# CH32X035G8U-R0.net
KiCad netlist of a schematic drawn in Altium Designer
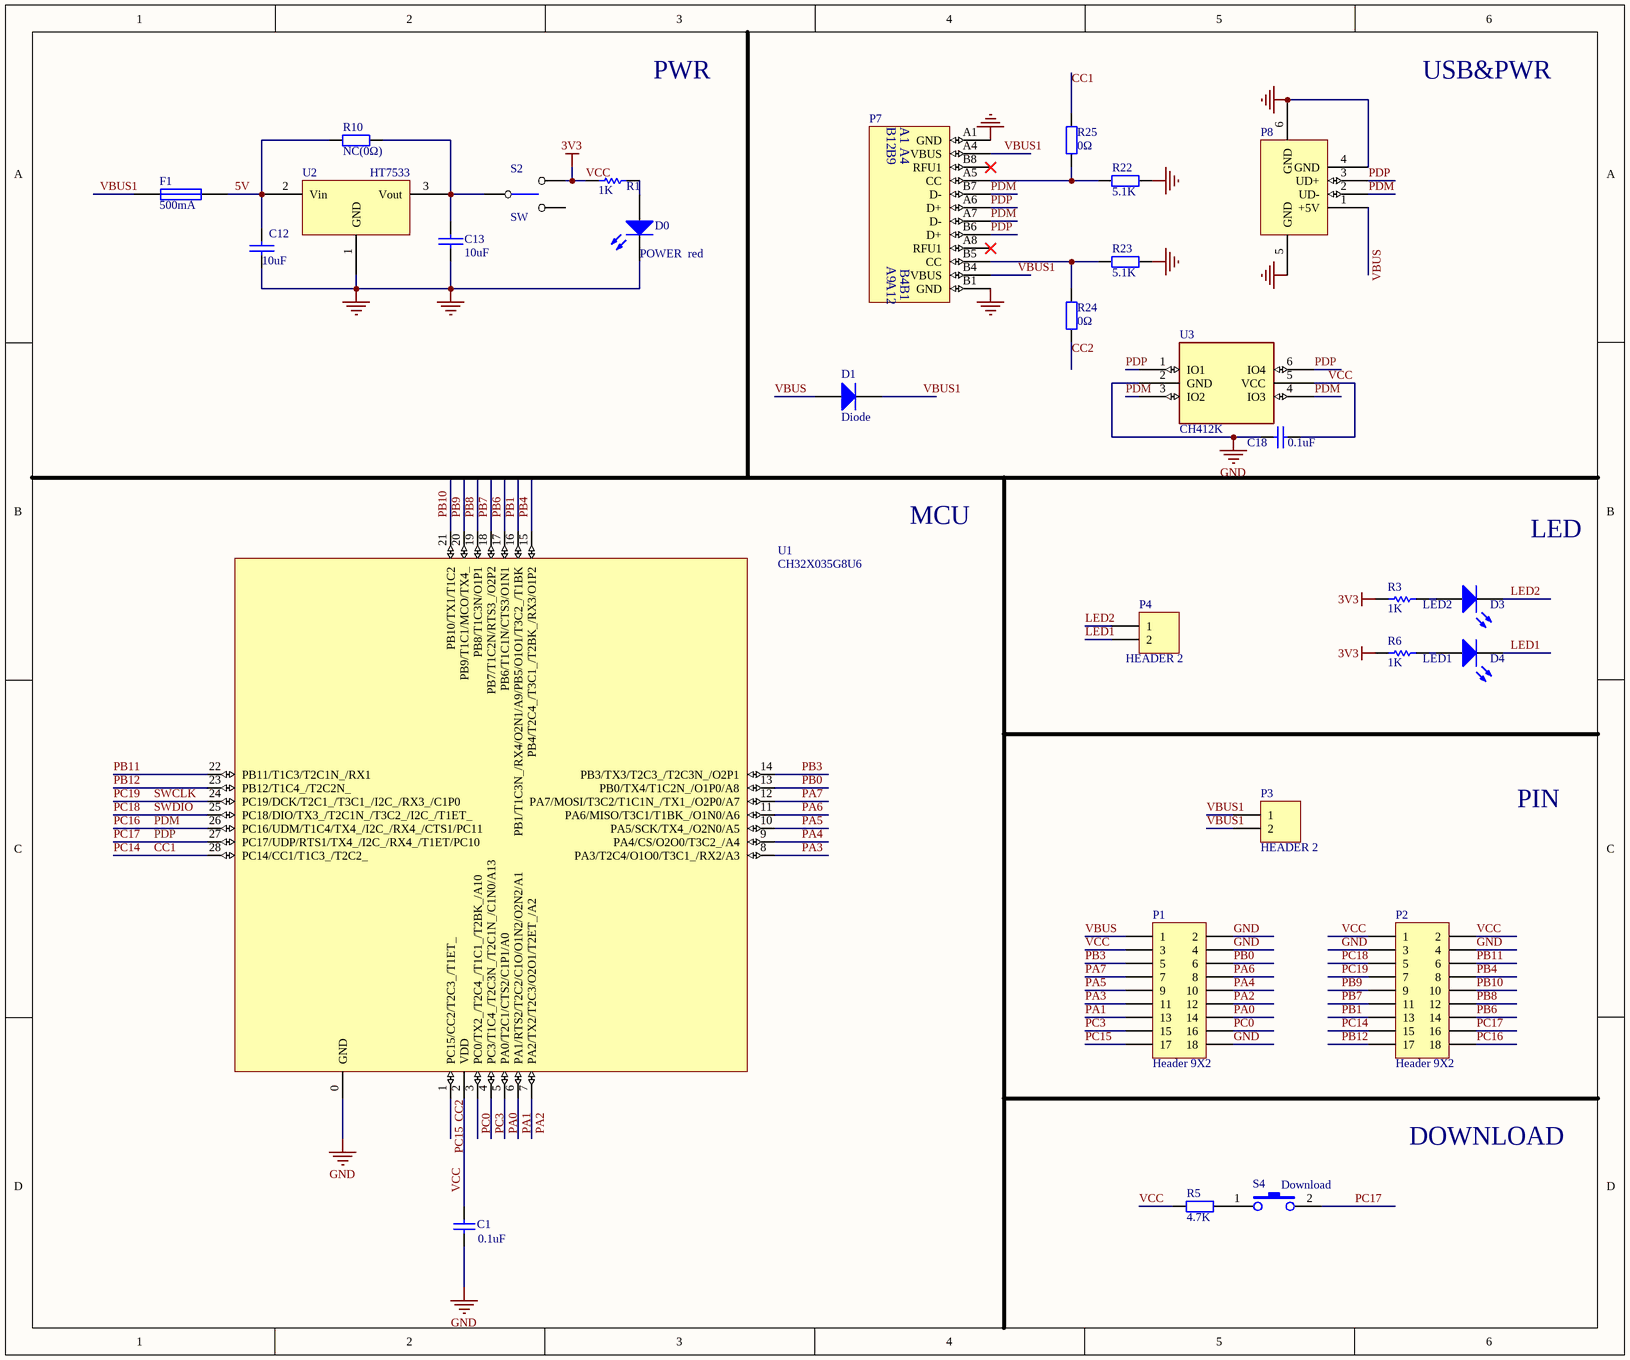
[diagram p0: CH32X035G8U-R0.SchDoc]

(export (version "E")
  (design (tool "Eeschema 10.0.6"))
  (components
    (comp (ref "C1")
      (value "0.1uF")
      (footprint "0603_C")
      (description "Capacitor")
      (libsource (lib "Miscellaneous Devices") (part "Cap"))
    )
    (comp (ref "C12")
      (value "10uF")
      (footprint "0603_C")
      (description "Capacitor")
      (libsource (lib "*") (part "CAP"))
    )
    (comp (ref "C13")
      (value "10uF")
      (footprint "0603_C")
      (description "Capacitor")
      (libsource (lib "*") (part "CAP"))
    )
    (comp (ref "C18")
      (value "0.1uF")
      (footprint "0603_C")
      (description "Capacitor")
      (libsource (lib "Miscellaneous Devices") (part "Cap"))
    )
    (comp (ref "D0")
      (value "POWER  red")
      (footprint "0603+")
      (description "Typical INFRARED GaAs LED")
      (fields (field (name "PUBLISHER") "Altium Limited"))
      (libsource (lib "*") (part "LED0"))
    )
    (comp (ref "D1")
      (value "Diode")
      (footprint "SOD-123")
      (description "Default Diode")
      (fields (field (name "PUBLISHER") "Altium Limited"))
      (libsource (lib "Miscellaneous Devices") (part "Diode"))
    )
    (comp (ref "D3")
      (value "LED2")
      (footprint "0603+")
      (description "Typical INFRARED GaAs LED")
      (fields (field (name "PUBLISHER") "Altium Limited"))
      (libsource (lib "*") (part "LED0"))
    )
    (comp (ref "D4")
      (value "LED1")
      (footprint "0603+")
      (description "Typical INFRARED GaAs LED")
      (fields (field (name "PUBLISHER") "Altium Limited"))
      (libsource (lib "*") (part "LED0"))
    )
    (comp (ref "F1")
      (value "500mA")
      (footprint "0603")
      (description "Fuse")
      (libsource (lib "*") (part "FUSE1"))
    )
    (comp (ref "P1")
      (value "Header 9X2")
      (footprint "IDC18-2.54mm")
      (description "Header, 9-Pin, Dual row")
      (fields (field (name "PUBLISHER") "Altium Limited"))
      (libsource (lib "Miscellaneous Connectors") (part "Header 9X2"))
    )
    (comp (ref "P2")
      (value "Header 9X2")
      (footprint "IDC18-2.54mm")
      (description "Header, 9-Pin, Dual row")
      (fields (field (name "PUBLISHER") "Altium Limited"))
      (libsource (lib "Miscellaneous Connectors") (part "Header 9X2"))
    )
    (comp (ref "P3")
      (value "HEADER 2")
      (footprint "MYPCB:SIP2-2.54mm")
      (description "Header, 2-Pin")
      (libsource (lib "wch_sch_others") (part "HEADER 2"))
    )
    (comp (ref "P4")
      (value "HEADER 2")
      (footprint "MYPCB:SIP2-2.54mm")
      (description "Header, 2-Pin")
      (libsource (lib "wch_sch_others") (part "HEADER 2"))
    )
    (comp (ref "P7")
      (value "TYPE-C")
      (footprint "TYPE-C-Receptacle-2.0")
      (libsource (lib "*") (part "TYPE-C1"))
    )
    (comp (ref "P8")
      (value "USB_A")
      (footprint "USBAF")
      (description "USB Port")
      (libsource (lib "*") (part "USB"))
    )
    (comp (ref "R1")
      (value "1K")
      (footprint "0603")
      (description "Semiconductor Resistor")
      (fields (field (name "PUBLISHER") "Altium Limited"))
      (libsource (lib "*") (part "Res Semi"))
    )
    (comp (ref "R3")
      (value "1K")
      (footprint "0603")
      (description "Semiconductor Resistor")
      (fields (field (name "PUBLISHER") "Altium Limited"))
      (libsource (lib "*") (part "Res Semi"))
    )
    (comp (ref "R5")
      (value "4.7K")
      (footprint "0603")
      (description "Resistor")
      (libsource (lib "Miscellaneous Devices") (part "Res2"))
    )
    (comp (ref "R6")
      (value "1K")
      (footprint "0603")
      (description "Semiconductor Resistor")
      (fields (field (name "PUBLISHER") "Altium Limited"))
      (libsource (lib "*") (part "Res Semi"))
    )
    (comp (ref "R10")
      (value "NC(0Ω)")
      (footprint "0603")
      (description "Resistor")
      (fields (field (name "PUBLISHER") "Altium Limited"))
      (libsource (lib "*") (part "Res2"))
    )
    (comp (ref "R22")
      (value "5.1K")
      (footprint "0603")
      (description "Resistor")
      (libsource (lib "Miscellaneous Devices") (part "Res2"))
    )
    (comp (ref "R23")
      (value "5.1K")
      (footprint "0603")
      (description "Resistor")
      (libsource (lib "Miscellaneous Devices") (part "Res2"))
    )
    (comp (ref "R24")
      (value "0Ω")
      (footprint "0603")
      (description "Resistor")
      (libsource (lib "") (part "Res2_1"))
    )
    (comp (ref "R25")
      (value "0Ω")
      (footprint "0603")
      (description "Resistor")
      (libsource (lib "") (part "Res2_1"))
    )
    (comp (ref "S2") (value "SW") (footprint "SW1") (libsource (lib "*") (part "SW")))
    (comp (ref "S4")
      (value "Download")
      (footprint "SMD_6.1x3.65x2.5mm-KEY")
      (libsource (lib "wch_sch_others") (part "KEY1"))
    )
    (comp (ref "U1")
      (value "CH32X035G8U6")
      (footprint "QFN28_4X4")
      (description "RISC-V MCU with USB/PD/ADC/SPI/I2C/UART/OA/CMP")
      (libsource (lib "CHXXX") (part "CH32X035G8U6"))
    )
    (comp (ref "U2")
      (value "HT7533")
      (footprint "SOT-89")
      (libsource (lib "wch_sch_others") (part "1117-3.3V"))
    )
    (comp (ref "U3")
      (value "CH412K")
      (footprint "SOT-363")
      (description "Qaud ESD protect, high speed")
      (libsource (lib "CHXXX") (part "CH412K"))
    )
  )
  (nets
    (net (code "1") (name "/5V") (class "Default")
      (node (ref "C12") (pin "1") (pinfunction "1_1") (pintype "passive"))
      (node (ref "F1") (pin "2") (pinfunction "2_2") (pintype "passive"))
      (node (ref "R10") (pin "2") (pinfunction "2_2") (pintype "passive"))
      (node (ref "U2") (pin "2") (pinfunction "Vin_2") (pintype "passive"))
    )
    (net (code "3") (name "/CC1") (class "Default")
      (node (ref "P2") (pin "15") (pinfunction "15_15") (pintype "passive"))
      (node (ref "R25") (pin "2") (pinfunction "2_2") (pintype "passive"))
      (node (ref "U1") (pin "28") (pinfunction "PC14/CC1/T1C3_/T2C2__28") (pintype "bidirectional"))
    )
    (net (code "4") (name "/CC2") (class "Default")
      (node (ref "P1") (pin "17") (pinfunction "17_17") (pintype "passive"))
      (node (ref "R24") (pin "1") (pinfunction "1_1") (pintype "passive"))
      (node (ref "U1") (pin "1") (pinfunction "PC15/CC2/T2C3_/T1ET__1") (pintype "bidirectional"))
    )
    (net (code "5") (name "/LED1") (class "Default")
      (node (ref "D4") (pin "2") (pinfunction "K_2") (pintype "passive"))
      (node (ref "P4") (pin "2") (pinfunction "2_2") (pintype "passive"))
    )
    (net (code "6") (name "/LED2") (class "Default")
      (node (ref "D3") (pin "2") (pinfunction "K_2") (pintype "passive"))
      (node (ref "P4") (pin "1") (pinfunction "1_1") (pintype "passive"))
    )
    (net (code "7") (name "/PA0") (class "Default")
      (node (ref "P1") (pin "14") (pinfunction "14_14") (pintype "passive"))
      (node (ref "U1") (pin "5") (pinfunction "PA0/T2C1/CTS2/C1P1/A0_5") (pintype "bidirectional"))
    )
    (net (code "8") (name "/PA1") (class "Default")
      (node (ref "P1") (pin "13") (pinfunction "13_13") (pintype "passive"))
      (node (ref "U1") (pin "6") (pinfunction "PA1/RTS2/T2C2/C1O/O1N2/O2N2/A1_6") (pintype "bidirectional"))
    )
    (net (code "9") (name "/PA2") (class "Default")
      (node (ref "P1") (pin "12") (pinfunction "12_12") (pintype "passive"))
      (node (ref "U1") (pin "7") (pinfunction "PA2/TX2/T2C3/O2O1/T2ET_/A2_7") (pintype "bidirectional"))
    )
    (net (code "10") (name "/PA3") (class "Default")
      (node (ref "P1") (pin "11") (pinfunction "11_11") (pintype "passive"))
      (node (ref "U1") (pin "8") (pinfunction "PA3/T2C4/O1O0/T3C1_/RX2/A3_8") (pintype "bidirectional"))
    )
    (net (code "11") (name "/PA4") (class "Default")
      (node (ref "P1") (pin "10") (pinfunction "10_10") (pintype "passive"))
      (node (ref "U1") (pin "9") (pinfunction "PA4/CS/O2O0/T3C2_/A4_9") (pintype "bidirectional"))
    )
    (net (code "12") (name "/PA5") (class "Default")
      (node (ref "P1") (pin "9") (pinfunction "9_9") (pintype "passive"))
      (node (ref "U1") (pin "10") (pinfunction "PA5/SCK/TX4_/O2N0/A5_10") (pintype "bidirectional"))
    )
    (net (code "13") (name "/PA6") (class "Default")
      (node (ref "P1") (pin "8") (pinfunction "8_8") (pintype "passive"))
      (node (ref "U1") (pin "11") (pinfunction "PA6/MISO/T3C1/T1BK_/O1N0/A6_11") (pintype "bidirectional"))
    )
    (net (code "14") (name "/PA7") (class "Default")
      (node (ref "P1") (pin "7") (pinfunction "7_7") (pintype "passive"))
      (node (ref "U1") (pin "12") (pinfunction "PA7/MOSI/T3C2/T1C1N_/TX1_/O2P0/A7_12") (pintype "bidirectional"))
    )
    (net (code "15") (name "/PB0") (class "Default")
      (node (ref "P1") (pin "6") (pinfunction "6_6") (pintype "passive"))
      (node (ref "U1") (pin "13") (pinfunction "PB0/TX4/T1C2N_/O1P0/A8_13") (pintype "bidirectional"))
    )
    (net (code "16") (name "/PB1") (class "Default")
      (node (ref "P2") (pin "13") (pinfunction "13_13") (pintype "passive"))
      (node (ref "U1") (pin "16") (pinfunction "PB1/T1C3N_/RX4/O2N1/A9/PB5/O1O1/T3C2_/T1BK_16") (pintype "bidirectional"))
    )
    (net (code "17") (name "/PB3") (class "Default")
      (node (ref "P1") (pin "5") (pinfunction "5_5") (pintype "passive"))
      (node (ref "U1") (pin "14") (pinfunction "PB3/TX3/T2C3_/T2C3N_/O2P1_14") (pintype "bidirectional"))
    )
    (net (code "18") (name "/PB4") (class "Default")
      (node (ref "P2") (pin "8") (pinfunction "8_8") (pintype "passive"))
      (node (ref "U1") (pin "15") (pinfunction "PB4/T2C4_/T3C1_/T2BK_/RX3/O1P2_15") (pintype "bidirectional"))
    )
    (net (code "19") (name "/PB6") (class "Default")
      (node (ref "P2") (pin "14") (pinfunction "14_14") (pintype "passive"))
      (node (ref "U1") (pin "17") (pinfunction "PB6/T1C1N/CTS3/O1N1_17") (pintype "bidirectional"))
    )
    (net (code "20") (name "/PB7") (class "Default")
      (node (ref "P2") (pin "11") (pinfunction "11_11") (pintype "passive"))
      (node (ref "U1") (pin "18") (pinfunction "PB7/T1C2N/RTS3_/O2P2_18") (pintype "bidirectional"))
    )
    (net (code "21") (name "/PB8") (class "Default")
      (node (ref "P2") (pin "12") (pinfunction "12_12") (pintype "passive"))
      (node (ref "U1") (pin "19") (pinfunction "PB8/T1C3N/O1P1_19") (pintype "bidirectional"))
    )
    (net (code "22") (name "/PB9") (class "Default")
      (node (ref "P2") (pin "9") (pinfunction "9_9") (pintype "passive"))
      (node (ref "U1") (pin "20") (pinfunction "PB9/T1C1/MCO/TX4__20") (pintype "bidirectional"))
    )
    (net (code "23") (name "/PB10") (class "Default")
      (node (ref "P2") (pin "10") (pinfunction "10_10") (pintype "passive"))
      (node (ref "U1") (pin "21") (pinfunction "PB10/TX1/T1C2_21") (pintype "bidirectional"))
    )
    (net (code "24") (name "/PB11") (class "Default")
      (node (ref "P2") (pin "6") (pinfunction "6_6") (pintype "passive"))
      (node (ref "U1") (pin "22") (pinfunction "PB11/T1C3/T2C1N_/RX1_22") (pintype "bidirectional"))
    )
    (net (code "25") (name "/PB12") (class "Default")
      (node (ref "P2") (pin "17") (pinfunction "17_17") (pintype "passive"))
      (node (ref "U1") (pin "23") (pinfunction "PB12/T1C4_/T2C2N__23") (pintype "bidirectional"))
    )
    (net (code "26") (name "/PC0") (class "Default")
      (node (ref "P1") (pin "16") (pinfunction "16_16") (pintype "passive"))
      (node (ref "U1") (pin "3") (pinfunction "PC0/TX2_/T2C4_/T1C1_/T2BK_/A10_3") (pintype "bidirectional"))
    )
    (net (code "27") (name "/PC3") (class "Default")
      (node (ref "P1") (pin "15") (pinfunction "15_15") (pintype "passive"))
      (node (ref "U1") (pin "4") (pinfunction "PC3/T1C4_/T2C3N_/T2C1N_/C1N0/A13_4") (pintype "bidirectional"))
    )
    (net (code "28") (name "/PC16") (class "Default")
      (node (ref "P2") (pin "18") (pinfunction "18_18") (pintype "passive"))
      (node (ref "P7") (pin "A7") (pinfunction "D-_A7") (pintype "bidirectional"))
      (node (ref "P7") (pin "B7") (pinfunction "D-_B7") (pintype "bidirectional"))
      (node (ref "P8") (pin "2") (pinfunction "UD-_2") (pintype "bidirectional"))
      (node (ref "U1") (pin "26") (pinfunction "PC16/UDM/T1C4/TX4_/I2C_/RX4_/CTS1/PC11_26") (pintype "bidirectional"))
      (node (ref "U3") (pin "3") (pinfunction "IO2_3") (pintype "bidirectional"))
      (node (ref "U3") (pin "4") (pinfunction "IO3_4") (pintype "bidirectional"))
    )
    (net (code "29") (name "/PC17") (class "Default")
      (node (ref "P2") (pin "16") (pinfunction "16_16") (pintype "passive"))
      (node (ref "P7") (pin "A6") (pinfunction "D+_A6") (pintype "bidirectional"))
      (node (ref "P7") (pin "B6") (pinfunction "D+_B6") (pintype "bidirectional"))
      (node (ref "P8") (pin "3") (pinfunction "UD+_3") (pintype "bidirectional"))
      (node (ref "S4") (pin "2") (pinfunction "2_2") (pintype "passive"))
      (node (ref "U1") (pin "27") (pinfunction "PC17/UDP/RTS1/TX4_/I2C_/RX4_/T1ET/PC10_27") (pintype "bidirectional"))
      (node (ref "U3") (pin "1") (pinfunction "IO1_1") (pintype "bidirectional"))
      (node (ref "U3") (pin "6") (pinfunction "IO4_6") (pintype "bidirectional"))
    )
    (net (code "30") (name "/PC18") (class "Default")
      (node (ref "P2") (pin "5") (pinfunction "5_5") (pintype "passive"))
      (node (ref "U1") (pin "25") (pinfunction "PC18/DIO/TX3_/T2C1N_/T3C2_/I2C_/T1ET__25") (pintype "bidirectional"))
    )
    (net (code "31") (name "/PC19") (class "Default")
      (node (ref "P2") (pin "7") (pinfunction "7_7") (pintype "passive"))
      (node (ref "U1") (pin "24") (pinfunction "PC19/DCK/T2C1_/T3C1_/I2C_/RX3_/C1P0_24") (pintype "bidirectional"))
    )
    (net (code "32") (name "/VBUS") (class "Default")
      (node (ref "D1") (pin "1") (pinfunction "A_1") (pintype "passive"))
      (node (ref "P1") (pin "1") (pinfunction "1_1") (pintype "passive"))
      (node (ref "P8") (pin "1") (pinfunction "+5V_1") (pintype "power_in"))
    )
    (net (code "33") (name "/VBUS1") (class "Default")
      (node (ref "D1") (pin "2") (pinfunction "K_2") (pintype "passive"))
      (node (ref "F1") (pin "1") (pinfunction "1_1") (pintype "passive"))
      (node (ref "P3") (pin "1") (pinfunction "1_1") (pintype "passive"))
      (node (ref "P3") (pin "2") (pinfunction "2_2") (pintype "passive"))
      (node (ref "P7") (pin "A4") (pinfunction "VBUS_A4") (pintype "bidirectional"))
      (node (ref "P7") (pin "B4") (pinfunction "VBUS_B4") (pintype "bidirectional"))
    )
    (net (code "34") (name "3V3") (class "Default")
      (node (ref "C1") (pin "2") (pinfunction "2_2") (pintype "passive"))
      (node (ref "C18") (pin "2") (pinfunction "2_2") (pintype "passive"))
      (node (ref "P1") (pin "3") (pinfunction "3_3") (pintype "passive"))
      (node (ref "P2") (pin "1") (pinfunction "1_1") (pintype "passive"))
      (node (ref "P2") (pin "2") (pinfunction "2_2") (pintype "passive"))
      (node (ref "R1") (pin "2") (pinfunction "2_2") (pintype "passive"))
      (node (ref "R3") (pin "1") (pinfunction "1_1") (pintype "passive"))
      (node (ref "R5") (pin "1") (pinfunction "1_1") (pintype "passive"))
      (node (ref "R6") (pin "1") (pinfunction "1_1") (pintype "passive"))
      (node (ref "S2") (pin "3") (pinfunction "3_3") (pintype "passive"))
      (node (ref "U1") (pin "2") (pinfunction "VDD_2") (pintype "power_in"))
      (node (ref "U3") (pin "5") (pinfunction "VCC_5") (pintype "power_in"))
    )
    (net (code "35") (name "GND") (class "Default")
      (node (ref "C1") (pin "1") (pinfunction "1_1") (pintype "passive"))
      (node (ref "C12") (pin "2") (pinfunction "2_2") (pintype "passive"))
      (node (ref "C13") (pin "2") (pinfunction "2_2") (pintype "passive"))
      (node (ref "C18") (pin "1") (pinfunction "1_1") (pintype "passive"))
      (node (ref "D0") (pin "2") (pinfunction "K_2") (pintype "passive"))
      (node (ref "P1") (pin "18") (pinfunction "18_18") (pintype "passive"))
      (node (ref "P1") (pin "2") (pinfunction "2_2") (pintype "passive"))
      (node (ref "P1") (pin "4") (pinfunction "4_4") (pintype "passive"))
      (node (ref "P2") (pin "3") (pinfunction "3_3") (pintype "passive"))
      (node (ref "P2") (pin "4") (pinfunction "4_4") (pintype "passive"))
      (node (ref "P7") (pin "A1") (pinfunction "GND_A1") (pintype "bidirectional"))
      (node (ref "P7") (pin "B1") (pinfunction "GND_B1") (pintype "bidirectional"))
      (node (ref "P8") (pin "4") (pinfunction "GND_4") (pintype "power_in"))
      (node (ref "P8") (pin "5") (pinfunction "GND_5") (pintype "power_in"))
      (node (ref "P8") (pin "6") (pinfunction "GND_6") (pintype "power_in"))
      (node (ref "R22") (pin "2") (pinfunction "2_2") (pintype "passive"))
      (node (ref "R23") (pin "2") (pinfunction "2_2") (pintype "passive"))
      (node (ref "U1") (pin "0") (pinfunction "GND_0") (pintype "power_in"))
      (node (ref "U2") (pin "1") (pinfunction "GND_1") (pintype "passive"))
      (node (ref "U3") (pin "2") (pinfunction "GND_2") (pintype "power_in"))
    )
    (net (code "36") (name "Net-(D0-A)") (class "Default")
      (node (ref "D0") (pin "1") (pinfunction "A_1") (pintype "passive"))
      (node (ref "R1") (pin "1") (pinfunction "1_1") (pintype "passive"))
    )
    (net (code "37") (name "Net-(D3-A)") (class "Default")
      (node (ref "D3") (pin "1") (pinfunction "A_1") (pintype "passive"))
      (node (ref "R3") (pin "2") (pinfunction "2_2") (pintype "passive"))
    )
    (net (code "38") (name "Net-(D4-A)") (class "Default")
      (node (ref "D4") (pin "1") (pinfunction "A_1") (pintype "passive"))
      (node (ref "R6") (pin "2") (pinfunction "2_2") (pintype "passive"))
    )
    (net (code "39") (name "Net-(P7-CC-PadA5)") (class "Default")
      (node (ref "P7") (pin "A5") (pinfunction "CC_A5") (pintype "bidirectional"))
      (node (ref "R22") (pin "1") (pinfunction "1_1") (pintype "passive"))
      (node (ref "R25") (pin "1") (pinfunction "1_1") (pintype "passive"))
    )
    (net (code "40") (name "Net-(P7-CC-PadB5)") (class "Default")
      (node (ref "P7") (pin "B5") (pinfunction "CC_B5") (pintype "bidirectional"))
      (node (ref "R23") (pin "1") (pinfunction "1_1") (pintype "passive"))
      (node (ref "R24") (pin "2") (pinfunction "2_2") (pintype "passive"))
    )
    (net (code "41") (name "Net-(R5-Pad2)") (class "Default")
      (node (ref "R5") (pin "2") (pinfunction "2_2") (pintype "passive"))
      (node (ref "S4") (pin "1") (pinfunction "1_1") (pintype "passive"))
    )
    (net (code "42") (name "Net-(U2-Vout)") (class "Default")
      (node (ref "C13") (pin "1") (pinfunction "1_1") (pintype "passive"))
      (node (ref "R10") (pin "1") (pinfunction "1_1") (pintype "passive"))
      (node (ref "S2") (pin "1") (pinfunction "1_1") (pintype "passive"))
      (node (ref "U2") (pin "3") (pinfunction "Vout_3") (pintype "passive"))
    )
    (net (code "43") (name "unconnected-(P7-RFU1-PadA8)") (class "Default")
      (node (ref "P7") (pin "A8") (pinfunction "RFU1_A8") (pintype "bidirectional+no_connect"))
    )
    (net (code "44") (name "unconnected-(P7-RFU1-PadB8)") (class "Default")
      (node (ref "P7") (pin "B8") (pinfunction "RFU1_B8") (pintype "bidirectional+no_connect"))
    )
    (net (code "45") (name "unconnected-(S2-Pad2)") (class "Default")
      (node (ref "S2") (pin "2") (pinfunction "2_2") (pintype "passive"))
    )
  )
)
